# XT-01_Power.net
KiCad netlist of a schematic drawn in EAGLE
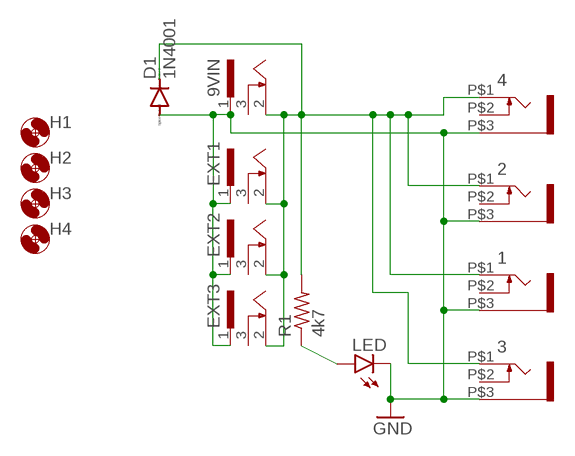
[diagram p0: schematic, sheet 1]

(export (version "E")
  (design (tool "Eeschema 10.0.6"))
  (components
    (comp (ref "1")
      (value "WQP-PJ301M-12_JACK")
      (footprint "eagle-import:WQP-PJ301M-12_JACK")
      (libsource (lib "eagle-import") (part "WQP-PJ301M-12_JACK"))
    )
    (comp (ref "2")
      (value "WQP-PJ301M-12_JACK")
      (footprint "eagle-import:WQP-PJ301M-12_JACK")
      (libsource (lib "eagle-import") (part "WQP-PJ301M-12_JACK"))
    )
    (comp (ref "3")
      (value "WQP-PJ301M-12_JACK")
      (footprint "eagle-import:WQP-PJ301M-12_JACK")
      (libsource (lib "eagle-import") (part "WQP-PJ301M-12_JACK"))
    )
    (comp (ref "4")
      (value "WQP-PJ301M-12_JACK")
      (footprint "eagle-import:WQP-PJ301M-12_JACK")
      (libsource (lib "eagle-import") (part "WQP-PJ301M-12_JACK"))
    )
    (comp (ref "9VIN")
      (value "SCD-014A")
      (footprint "eagle-import:SCD-014-A")
      (libsource (lib "eagle-import") (part "SCD-014A"))
    )
    (comp (ref "D1")
      (value "1N4001")
      (footprint "eagle-import:DO41-10")
      (libsource (lib "eagle-import") (part "1N4004"))
    )
    (comp (ref "EXT1")
      (value "SCD-014A")
      (footprint "eagle-import:SCD-014-A")
      (libsource (lib "eagle-import") (part "SCD-014A"))
    )
    (comp (ref "EXT2")
      (value "SCD-014A")
      (footprint "eagle-import:SCD-014-A")
      (libsource (lib "eagle-import") (part "SCD-014A"))
    )
    (comp (ref "EXT3")
      (value "SCD-014A")
      (footprint "eagle-import:SCD-014-A")
      (libsource (lib "eagle-import") (part "SCD-014A"))
    )
    (comp (ref "H1")
      (value "MOUNT-HOLE3.0")
      (footprint "eagle-import:3,0")
      (libsource (lib "eagle-import") (part "MOUNT-HOLE3.0"))
    )
    (comp (ref "H2")
      (value "MOUNT-HOLE3.0")
      (footprint "eagle-import:3,0")
      (libsource (lib "eagle-import") (part "MOUNT-HOLE3.0"))
    )
    (comp (ref "H3")
      (value "MOUNT-HOLE3.0")
      (footprint "eagle-import:3,0")
      (libsource (lib "eagle-import") (part "MOUNT-HOLE3.0"))
    )
    (comp (ref "H4")
      (value "MOUNT-HOLE3.0")
      (footprint "eagle-import:3,0")
      (libsource (lib "eagle-import") (part "MOUNT-HOLE3.0"))
    )
    (comp (ref "LED")
      (value "LED3MM")
      (footprint "eagle-import:LED3MM")
      (libsource (lib "eagle-import") (part "LED3MM"))
    )
    (comp (ref "R1")
      (value "4k7")
      (footprint "eagle-import:0207_7")
      (libsource (lib "eagle-import") (part "R-US_0207/7"))
    )
  )
  (nets
    (net (code "1") (name "GND") (class "Default")
      (node (ref "1") (pin "P$3") (pinfunction "1_P$3") (pintype "passive"))
      (node (ref "2") (pin "P$3") (pinfunction "1_P$3") (pintype "passive"))
      (node (ref "3") (pin "P$3") (pinfunction "1_P$3") (pintype "passive"))
      (node (ref "4") (pin "P$3") (pinfunction "1_P$3") (pintype "passive"))
      (node (ref "9VIN") (pin "1") (pinfunction "1_1") (pintype "passive"))
      (node (ref "D1") (pin "A") (pinfunction "A_A") (pintype "passive"))
      (node (ref "EXT1") (pin "1") (pinfunction "1_1") (pintype "passive"))
      (node (ref "EXT2") (pin "1") (pinfunction "1_1") (pintype "passive"))
      (node (ref "EXT3") (pin "1") (pinfunction "1_1") (pintype "passive"))
      (node (ref "LED") (pin "K") (pinfunction "C_K") (pintype "passive"))
    )
    (net (code "2") (name "Net-(1-2)") (class "Default")
      (node (ref "1") (pin "P$1") (pinfunction "2_P$1") (pintype "passive"))
      (node (ref "2") (pin "P$1") (pinfunction "2_P$1") (pintype "passive"))
      (node (ref "3") (pin "P$1") (pinfunction "2_P$1") (pintype "passive"))
      (node (ref "4") (pin "P$1") (pinfunction "2_P$1") (pintype "passive"))
      (node (ref "9VIN") (pin "2") (pinfunction "2_2") (pintype "passive"))
      (node (ref "D1") (pin "C") (pinfunction "C_C") (pintype "passive"))
      (node (ref "EXT1") (pin "2") (pinfunction "2_2") (pintype "passive"))
      (node (ref "EXT2") (pin "2") (pinfunction "2_2") (pintype "passive"))
      (node (ref "EXT3") (pin "2") (pinfunction "2_2") (pintype "passive"))
      (node (ref "R1") (pin "2") (pinfunction "2_2") (pintype "passive"))
    )
    (net (code "3") (name "Net-(LED-PadA)") (class "Default")
      (node (ref "LED") (pin "A") (pinfunction "A_A") (pintype "passive"))
      (node (ref "R1") (pin "1") (pinfunction "1_1") (pintype "passive"))
    )
    (net (code "4") (name "unconnected-(1-3-PadP$2)") (class "Default")
      (node (ref "1") (pin "P$2") (pinfunction "3_P$2") (pintype "passive"))
    )
    (net (code "5") (name "unconnected-(2-3-PadP$2)") (class "Default")
      (node (ref "2") (pin "P$2") (pinfunction "3_P$2") (pintype "passive"))
    )
    (net (code "6") (name "unconnected-(3-3-PadP$2)") (class "Default")
      (node (ref "3") (pin "P$2") (pinfunction "3_P$2") (pintype "passive"))
    )
    (net (code "7") (name "unconnected-(4-3-PadP$2)") (class "Default")
      (node (ref "4") (pin "P$2") (pinfunction "3_P$2") (pintype "passive"))
    )
    (net (code "8") (name "unconnected-(9VIN-Pad3)") (class "Default")
      (node (ref "9VIN") (pin "3") (pinfunction "3_3") (pintype "passive"))
    )
    (net (code "9") (name "unconnected-(EXT1-Pad3)") (class "Default")
      (node (ref "EXT1") (pin "3") (pinfunction "3_3") (pintype "passive"))
    )
    (net (code "10") (name "unconnected-(EXT2-Pad3)") (class "Default")
      (node (ref "EXT2") (pin "3") (pinfunction "3_3") (pintype "passive"))
    )
    (net (code "11") (name "unconnected-(EXT3-Pad3)") (class "Default")
      (node (ref "EXT3") (pin "3") (pinfunction "3_3") (pintype "passive"))
    )
  )
)
